# FIT_TCM_ATxmega.net
KiCad netlist of a schematic drawn in Altium Designer
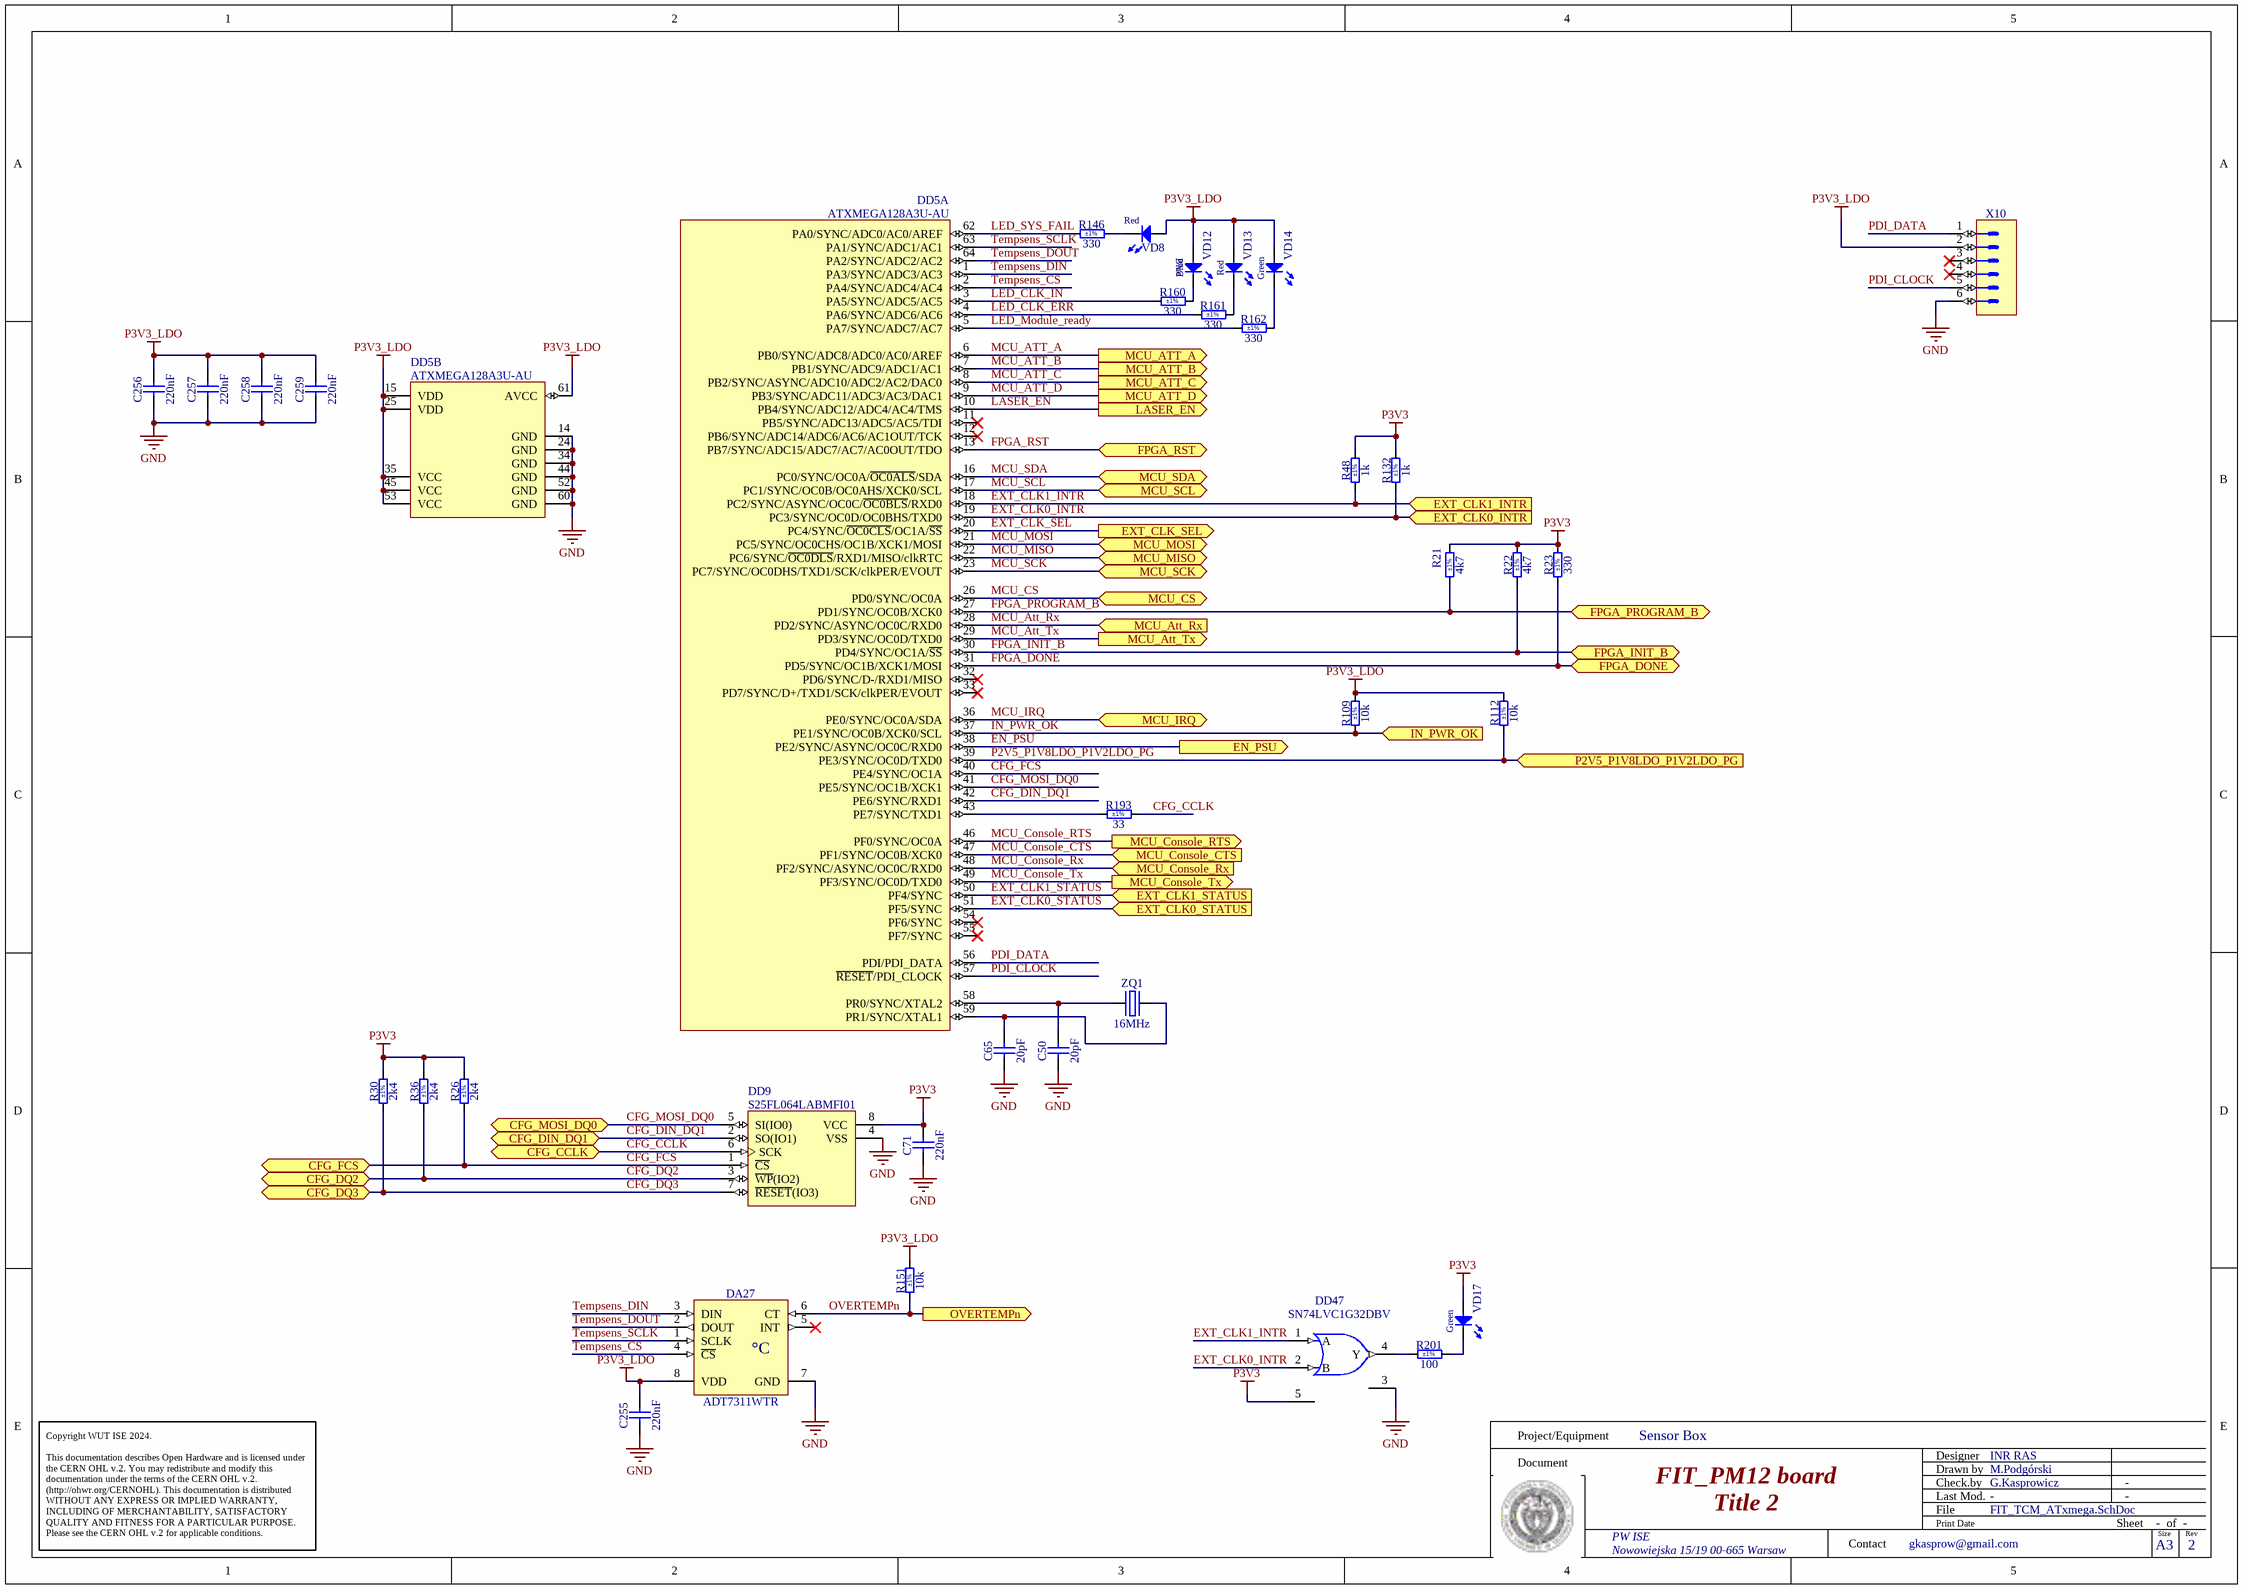
[diagram p0: FIT_TCM_ATxmega.SchDoc]

(export (version "E")
  (design (tool "Eeschema 10.0.6"))
  (components
    (comp (ref "C50")
      (value "20pF")
      (footprint "CAPC2012X135N")
      (description "Non-polarised capacitor")
      (fields
        (field (name "PART NUMBER") "CC0805_20PF_50V_2%_C0G")
        (field (name "VOLTAGE") "50V")
        (field (name "AUTHOR") "CERN DEM HF")
      )
      (libsource (lib "Capacitors") (part "Capacitor - non polarized"))
    )
    (comp (ref "C65")
      (value "20pF")
      (footprint "CAPC2012X135N")
      (description "Non-polarised capacitor")
      (fields
        (field (name "PART NUMBER") "CC0805_20PF_50V_2%_C0G")
        (field (name "VOLTAGE") "50V")
        (field (name "AUTHOR") "CERN DEM HF")
      )
      (libsource (lib "Capacitors") (part "Capacitor - non polarized"))
    )
    (comp (ref "C71")
      (value "220nF")
      (footprint "CAPC2012X135N")
      (description "Non-polarised capacitor")
      (fields
        (field (name "PART NUMBER") "CC0805_220NF_50V_10%_X7R")
        (field (name "VOLTAGE") "50V")
        (field (name "AUTHOR") "CERN DEM JLC")
      )
      (libsource (lib "Capacitors") (part "Capacitor - non polarized"))
    )
    (comp (ref "C255")
      (value "220nF")
      (footprint "CAPC2012X135N")
      (description "Non-polarised capacitor")
      (fields
        (field (name "PART NUMBER") "CC0805_220NF_50V_10%_X7R")
        (field (name "VOLTAGE") "50V")
        (field (name "AUTHOR") "CERN DEM JLC")
      )
      (libsource (lib "Capacitors") (part "Capacitor - non polarized"))
    )
    (comp (ref "C256")
      (value "220nF")
      (footprint "CAPC2012X135N")
      (description "Non-polarised capacitor")
      (fields
        (field (name "PART NUMBER") "CC0805_220NF_50V_10%_X7R")
        (field (name "VOLTAGE") "50V")
        (field (name "AUTHOR") "CERN DEM JLC")
      )
      (libsource (lib "Capacitors") (part "Capacitor - non polarized"))
    )
    (comp (ref "C257")
      (value "220nF")
      (footprint "CAPC2012X135N")
      (description "Non-polarised capacitor")
      (fields
        (field (name "PART NUMBER") "CC0805_220NF_50V_10%_X7R")
        (field (name "VOLTAGE") "50V")
        (field (name "AUTHOR") "CERN DEM JLC")
      )
      (libsource (lib "Capacitors") (part "Capacitor - non polarized"))
    )
    (comp (ref "C258")
      (value "220nF")
      (footprint "CAPC2012X135N")
      (description "Non-polarised capacitor")
      (fields
        (field (name "PART NUMBER") "CC0805_220NF_50V_10%_X7R")
        (field (name "VOLTAGE") "50V")
        (field (name "AUTHOR") "CERN DEM JLC")
      )
      (libsource (lib "Capacitors") (part "Capacitor - non polarized"))
    )
    (comp (ref "C259")
      (value "220nF")
      (footprint "CAPC2012X135N")
      (description "Non-polarised capacitor")
      (fields
        (field (name "PART NUMBER") "CC0805_220NF_50V_10%_X7R")
        (field (name "VOLTAGE") "50V")
        (field (name "AUTHOR") "CERN DEM JLC")
      )
      (libsource (lib "Capacitors") (part "Capacitor - non polarized"))
    )
    (comp (ref "DA27")
      (value "ADT7311WTR")
      (footprint "SOIC127P600X175-8N")
      (description "±0.5°C Accurate, 16-Bit Digital SPI Temperature Sensor")
      (fields (field (name "MANUFACTURER") "ANALOG DEVICES") (field (name "AUTHOR") "CERN DEM HF"))
      (libsource (lib "ICs And Semiconductors") (part "ADT7311WTR"))
    )
    (comp (ref "DD5")
      (value "ATXMEGA128A3U-AU")
      (footprint "QFP80P1600X1600X120-64N")
      (description "8/16-bit XMEGA A3BU 32MHz Microcontroller With 256KBytes of in-System Self-Programmable Flash")
      (fields (field (name "MANUFACTURER") "MICROCHIP TECHNOLOGY") (field (name "AUTHOR") "CERN DEM HF"))
      (libsource (lib "") (part "ATXMEGA128A3U-AU_1"))
    )
    (comp (ref "DD9")
      (value "S25FL064LABMFI01")
      (footprint "SOIC127P800X216-8N")
      (description "64 Mb (8 MB), 3V, FL-L SPI Flash Memory")
      (fields (field (name "MANUFACTURER") "INFINEON") (field (name "AUTHOR") "CERN DEM HF"))
      (libsource (lib "ICs And Semiconductors") (part "S25FL064LABMFI01"))
    )
    (comp (ref "DD47")
      (value "SN74LVC1G32DBV")
      (footprint "SOT95P280X145-5N")
      (description "Single 2-Input Positive-OR Gate")
      (fields
        (field (name "PART NUMBER") "SN74LVC1G32DBVR")
        (field (name "MANUFACTURER") "TEXAS INSTRUMENTS")
        (field (name "AUTHOR") "CERN DEM JLC")
      )
      (libsource (lib "ICs And Semiconductors") (part "741G32"))
    )
    (comp (ref "R21")
      (value "4k7")
      (footprint "RESC2012X60N")
      (description "Resistor - 1%")
      (fields
        (field (name "TOLERANCE") "±1%")
        (field (name "PART NUMBER") "R0805_4K7_1%_0.125W_100PPM")
        (field (name "POWER") "0.125W")
        (field (name "AUTHOR") "CERN DEM JLC")
      )
      (libsource (lib "Resistors") (part "Resistor - 1%"))
    )
    (comp (ref "R22")
      (value "4k7")
      (footprint "RESC2012X60N")
      (description "Resistor - 1%")
      (fields
        (field (name "TOLERANCE") "±1%")
        (field (name "PART NUMBER") "R0805_4K7_1%_0.125W_100PPM")
        (field (name "POWER") "0.125W")
        (field (name "AUTHOR") "CERN DEM JLC")
      )
      (libsource (lib "Resistors") (part "Resistor - 1%"))
    )
    (comp (ref "R23")
      (value "330")
      (footprint "RESC2012X60N")
      (description "Resistor - 1%")
      (fields
        (field (name "TOLERANCE") "±1%")
        (field (name "PART NUMBER") "R0805_330R_1%_0.125W_100PPM")
        (field (name "POWER") "0.125W")
        (field (name "AUTHOR") "CERN DEM JLC")
      )
      (libsource (lib "Resistors") (part "Resistor - 1%"))
    )
    (comp (ref "R26")
      (value "2k4")
      (footprint "RESC2012X60N")
      (description "Resistor - 1%")
      (fields
        (field (name "TOLERANCE") "±1%")
        (field (name "PART NUMBER") "R0805_2K4_1%_0.125W_100PPM")
        (field (name "POWER") "0.125W")
        (field (name "AUTHOR") "CERN DEM JLC")
      )
      (libsource (lib "Resistors") (part "Resistor - 1%"))
    )
    (comp (ref "R30")
      (value "2k4")
      (footprint "RESC2012X60N")
      (description "Resistor - 1%")
      (fields
        (field (name "TOLERANCE") "±1%")
        (field (name "PART NUMBER") "R0805_2K4_1%_0.125W_100PPM")
        (field (name "POWER") "0.125W")
        (field (name "AUTHOR") "CERN DEM JLC")
      )
      (libsource (lib "Resistors") (part "Resistor - 1%"))
    )
    (comp (ref "R36")
      (value "2k4")
      (footprint "RESC2012X60N")
      (description "Resistor - 1%")
      (fields
        (field (name "TOLERANCE") "±1%")
        (field (name "PART NUMBER") "R0805_2K4_1%_0.125W_100PPM")
        (field (name "POWER") "0.125W")
        (field (name "AUTHOR") "CERN DEM JLC")
      )
      (libsource (lib "Resistors") (part "Resistor - 1%"))
    )
    (comp (ref "R48")
      (value "1k")
      (footprint "RESC2012X60N")
      (description "Resistor - 1%")
      (fields
        (field (name "TOLERANCE") "±1%")
        (field (name "PART NUMBER") "R0805_1K_1%_0.125W_100PPM")
        (field (name "POWER") "0.125W")
        (field (name "AUTHOR") "CERN DEM JLC")
      )
      (libsource (lib "Resistors") (part "Resistor - 1%"))
    )
    (comp (ref "R109")
      (value "10k")
      (footprint "RESC2012X60N")
      (description "Resistor - 1%")
      (fields
        (field (name "TOLERANCE") "±1%")
        (field (name "PART NUMBER") "R0805_10K_1%_0.125W_100PPM")
        (field (name "POWER") "0.125W")
        (field (name "AUTHOR") "CERN DEM JLC")
      )
      (libsource (lib "Resistors") (part "Resistor - 1%"))
    )
    (comp (ref "R112")
      (value "10k")
      (footprint "RESC2012X60N")
      (description "Resistor - 1%")
      (fields
        (field (name "TOLERANCE") "±1%")
        (field (name "PART NUMBER") "R0805_10K_1%_0.125W_100PPM")
        (field (name "POWER") "0.125W")
        (field (name "AUTHOR") "CERN DEM JLC")
      )
      (libsource (lib "Resistors") (part "Resistor - 1%"))
    )
    (comp (ref "R132")
      (value "1k")
      (footprint "RESC2012X60N")
      (description "Resistor - 1%")
      (fields
        (field (name "TOLERANCE") "±1%")
        (field (name "PART NUMBER") "R0805_1K_1%_0.125W_100PPM")
        (field (name "POWER") "0.125W")
        (field (name "AUTHOR") "CERN DEM JLC")
      )
      (libsource (lib "Resistors") (part "Resistor - 1%"))
    )
    (comp (ref "R146")
      (value "330")
      (footprint "RESC2012X60N")
      (description "Resistor - 1%")
      (fields
        (field (name "TOLERANCE") "±1%")
        (field (name "PART NUMBER") "R0805_330R_1%_0.125W_100PPM")
        (field (name "POWER") "0.125W")
        (field (name "AUTHOR") "CERN DEM JLC")
      )
      (libsource (lib "Resistors") (part "Resistor - 1%"))
    )
    (comp (ref "R151")
      (value "10k")
      (footprint "RESC2012X60N")
      (description "Resistor - 1%")
      (fields
        (field (name "TOLERANCE") "±1%")
        (field (name "PART NUMBER") "R0805_10K_1%_0.125W_100PPM")
        (field (name "POWER") "0.125W")
        (field (name "AUTHOR") "CERN DEM JLC")
      )
      (libsource (lib "Resistors") (part "Resistor - 1%"))
    )
    (comp (ref "R160")
      (value "330")
      (footprint "RESC2012X60N")
      (description "Resistor - 1%")
      (fields
        (field (name "TOLERANCE") "±1%")
        (field (name "PART NUMBER") "R0805_330R_1%_0.125W_100PPM")
        (field (name "POWER") "0.125W")
        (field (name "AUTHOR") "CERN DEM JLC")
      )
      (libsource (lib "Resistors") (part "Resistor - 1%"))
    )
    (comp (ref "R161")
      (value "330")
      (footprint "RESC2012X60N")
      (description "Resistor - 1%")
      (fields
        (field (name "TOLERANCE") "±1%")
        (field (name "PART NUMBER") "R0805_330R_1%_0.125W_100PPM")
        (field (name "POWER") "0.125W")
        (field (name "AUTHOR") "CERN DEM JLC")
      )
      (libsource (lib "Resistors") (part "Resistor - 1%"))
    )
    (comp (ref "R162")
      (value "330")
      (footprint "RESC2012X60N")
      (description "Resistor - 1%")
      (fields
        (field (name "TOLERANCE") "±1%")
        (field (name "PART NUMBER") "R0805_330R_1%_0.125W_100PPM")
        (field (name "POWER") "0.125W")
        (field (name "AUTHOR") "CERN DEM JLC")
      )
      (libsource (lib "Resistors") (part "Resistor - 1%"))
    )
    (comp (ref "R193")
      (value "33")
      (footprint "RESC2012X60N")
      (description "Resistor - 1%")
      (fields
        (field (name "TOLERANCE") "±1%")
        (field (name "PART NUMBER") "R0805_33R_1%_0.125W_100PPM")
        (field (name "POWER") "0.125W")
        (field (name "AUTHOR") "CERN DEM JLC")
      )
      (libsource (lib "Resistors") (part "Resistor - 1%"))
    )
    (comp (ref "R201")
      (value "100")
      (footprint "RESC2012X60N")
      (description "Resistor - 1%")
      (fields
        (field (name "TOLERANCE") "±1%")
        (field (name "PART NUMBER") "R0805_100R_1%_0.125W_100PPM")
        (field (name "POWER") "0.125W")
        (field (name "AUTHOR") "CERN DEM JLC")
      )
      (libsource (lib "Resistors") (part "Resistor - 1%"))
    )
    (comp (ref "VD8")
      (value "Red")
      (footprint "LED_KINGBRIGHT_KPT-2012SURCK")
      (description "LED Red 1C 2A")
      (fields
        (field (name "PART NUMBER") "LED_KINGBRIGHT_KPT-2012SURCK")
        (field (name "MANUFACTURER") "KINGBRIGHT")
        (field (name "AUTHOR") "CERN DEM BC")
      )
      (libsource (lib "ICs And Semiconductors") (part "LED Red 1C 2A"))
    )
    (comp (ref "VD12")
      (value "Blue")
      (footprint "LED_KINGBRIGHT_KPT-2012VBC-D")
      (description "LED Blue 1C 2A")
      (fields
        (field (name "PART NUMBER") "LED_KINGBRIGHT_KPT-2012VBC-D")
        (field (name "MANUFACTURER") "KINGBRIGHT")
        (field (name "AUTHOR") "CERN DEM BC")
      )
      (libsource (lib "ICs And Semiconductors") (part "LED Blue 1C 2A"))
    )
    (comp (ref "VD13")
      (value "Red")
      (footprint "LED_KINGBRIGHT_KPT-2012SURCK")
      (description "LED Red 1C 2A")
      (fields
        (field (name "PART NUMBER") "LED_KINGBRIGHT_KPT-2012SURCK")
        (field (name "MANUFACTURER") "KINGBRIGHT")
        (field (name "AUTHOR") "CERN DEM BC")
      )
      (libsource (lib "ICs And Semiconductors") (part "LED Red 1C 2A"))
    )
    (comp (ref "VD14")
      (value "Green")
      (footprint "LED_KINGBRIGHT_KP-2012LSGC")
      (description "LED Green 1C 2A")
      (fields
        (field (name "PART NUMBER") "LED_KINGBRIGHT_KP-2012LSGC")
        (field (name "MANUFACTURER") "KINGBRIGHT")
        (field (name "AUTHOR") "CERN DEM BC")
      )
      (libsource (lib "ICs And Semiconductors") (part "LED Green 1C 2A"))
    )
    (comp (ref "VD17")
      (value "Green")
      (footprint "LED_KINGBRIGHT_KP-2012LSGC")
      (description "LED Green 1C 2A")
      (fields
        (field (name "PART NUMBER") "LED_KINGBRIGHT_KP-2012LSGC")
        (field (name "MANUFACTURER") "KINGBRIGHT")
        (field (name "AUTHOR") "CERN DEM BC")
      )
      (libsource (lib "ICs And Semiconductors") (part "LED Green 1C 2A"))
    )
    (comp (ref "X10")
      (value "~")
      (footprint "CONNFLY_DS1013-06SSIB1-B-0")
      (description "Connector 6 Male")
      (fields
        (field (name "PART NUMBER") "CONNFLY_DS1013-06SSIB1-B-0")
        (field (name "MANUFACTURER") "CONNFLY")
        (field (name "AUTHOR") "CERN DEM HF")
      )
      (libsource (lib "Connectors") (part "Connector 6 Male"))
    )
    (comp (ref "ZQ1")
      (value "16MHz")
      (footprint "XTAL_ABRACON_ABL")
      (description "Quartz Crystal")
      (fields
        (field (name "PART NUMBER") "XTAL_16MHZ_ABRACON_ABL-16.000MHZ-B1U")
        (field (name "MANUFACTURER") "ABRACON")
        (field (name "AUTHOR") "CERN DEM HF")
      )
      (libsource (lib "ICs And Semiconductors") (part "Quartz Crystal"))
    )
  )
  (nets
    (net (code "1") (name "/CFG_CCLK") (class "Default")
      (node (ref "DD9") (pin "6") (pinfunction "SCK_6") (pintype "input"))
      (node (ref "R193") (pin "2") (pinfunction "2_2") (pintype "passive"))
    )
    (net (code "2") (name "/CFG_DIN_DQ1") (class "Default")
      (node (ref "DD5") (pin "42") (pinfunction "PE6/SYNC/RXD1_42") (pintype "bidirectional"))
      (node (ref "DD9") (pin "2") (pinfunction "SO(IO1)_2") (pintype "bidirectional"))
    )
    (net (code "3") (name "/CFG_DQ2") (class "Default")
      (node (ref "DD9") (pin "3") (pinfunction "~{WP}(IO2)_3") (pintype "bidirectional"))
      (node (ref "R36") (pin "1") (pinfunction "1_1") (pintype "passive"))
    )
    (net (code "4") (name "/CFG_DQ3") (class "Default")
      (node (ref "DD9") (pin "7") (pinfunction "~{RESET}(IO3)_7") (pintype "bidirectional"))
      (node (ref "R30") (pin "1") (pinfunction "1_1") (pintype "passive"))
    )
    (net (code "5") (name "/CFG_FCS") (class "Default")
      (node (ref "DD5") (pin "40") (pinfunction "PE4/SYNC/OC1A_40") (pintype "bidirectional"))
      (node (ref "DD9") (pin "1") (pinfunction "~{CS}_1") (pintype "input"))
      (node (ref "R26") (pin "1") (pinfunction "1_1") (pintype "passive"))
    )
    (net (code "6") (name "/CFG_MOSI_DQ0") (class "Default")
      (node (ref "DD5") (pin "41") (pinfunction "PE5/SYNC/OC1B/XCK1_41") (pintype "bidirectional"))
      (node (ref "DD9") (pin "5") (pinfunction "SI(IO0)_5") (pintype "bidirectional"))
    )
    (net (code "7") (name "/EN_PSU") (class "Default")
      (node (ref "DD5") (pin "38") (pinfunction "PE2/SYNC/ASYNC/OC0C/RXD0_38") (pintype "bidirectional"))
    )
    (net (code "8") (name "/EXT_CLK0_INTR") (class "Default")
      (node (ref "DD47") (pin "2") (pinfunction "B_2") (pintype "input"))
      (node (ref "DD5") (pin "19") (pinfunction "PC3/SYNC/OC0D/OC0BHS/TXD0_19") (pintype "bidirectional"))
      (node (ref "R132") (pin "1") (pinfunction "1_1") (pintype "passive"))
    )
    (net (code "9") (name "/EXT_CLK0_STATUS") (class "Default")
      (node (ref "DD5") (pin "51") (pinfunction "PF5/SYNC_51") (pintype "bidirectional"))
    )
    (net (code "10") (name "/EXT_CLK1_INTR") (class "Default")
      (node (ref "DD47") (pin "1") (pinfunction "A_1") (pintype "input"))
      (node (ref "DD5") (pin "18") (pinfunction "PC2/SYNC/ASYNC/OC0C/~{OC0BLS}/RXD0_18") (pintype "bidirectional"))
      (node (ref "R48") (pin "1") (pinfunction "1_1") (pintype "passive"))
    )
    (net (code "11") (name "/EXT_CLK1_STATUS") (class "Default")
      (node (ref "DD5") (pin "50") (pinfunction "PF4/SYNC_50") (pintype "bidirectional"))
    )
    (net (code "12") (name "/EXT_CLK_SEL") (class "Default")
      (node (ref "DD5") (pin "20") (pinfunction "PC4/SYNC/~{OC0CLS}/OC1A/~{SS}_20") (pintype "bidirectional"))
    )
    (net (code "13") (name "/FPGA_DONE") (class "Default")
      (node (ref "DD5") (pin "31") (pinfunction "PD5/SYNC/OC1B/XCK1/MOSI_31") (pintype "bidirectional"))
      (node (ref "R23") (pin "1") (pinfunction "1_1") (pintype "passive"))
    )
    (net (code "14") (name "/FPGA_INIT_B") (class "Default")
      (node (ref "DD5") (pin "30") (pinfunction "PD4/SYNC/OC1A/~{SS}_30") (pintype "bidirectional"))
      (node (ref "R22") (pin "1") (pinfunction "1_1") (pintype "passive"))
    )
    (net (code "15") (name "/FPGA_PROGRAM_B") (class "Default")
      (node (ref "DD5") (pin "27") (pinfunction "PD1/SYNC/OC0B/XCK0_27") (pintype "bidirectional"))
      (node (ref "R21") (pin "1") (pinfunction "1_1") (pintype "passive"))
    )
    (net (code "16") (name "/FPGA_RST") (class "Default")
      (node (ref "DD5") (pin "13") (pinfunction "PB7/SYNC/ADC15/ADC7/AC7/AC0OUT/TDO_13") (pintype "bidirectional"))
    )
    (net (code "17") (name "/IN_PWR_OK") (class "Default")
      (node (ref "DD5") (pin "37") (pinfunction "PE1/SYNC/OC0B/XCK0/SCL_37") (pintype "bidirectional"))
      (node (ref "R109") (pin "1") (pinfunction "1_1") (pintype "passive"))
    )
    (net (code "18") (name "/LASER_EN") (class "Default")
      (node (ref "DD5") (pin "10") (pinfunction "PB4/SYNC/ADC12/ADC4/AC4/TMS_10") (pintype "bidirectional"))
    )
    (net (code "19") (name "/LED_CLK_ERR") (class "Default")
      (node (ref "DD5") (pin "4") (pinfunction "PA6/SYNC/ADC6/AC6_4") (pintype "bidirectional"))
      (node (ref "R161") (pin "1") (pinfunction "1_1") (pintype "passive"))
    )
    (net (code "20") (name "/LED_CLK_IN") (class "Default")
      (node (ref "DD5") (pin "3") (pinfunction "PA5/SYNC/ADC5/AC5_3") (pintype "bidirectional"))
      (node (ref "R160") (pin "1") (pinfunction "1_1") (pintype "passive"))
    )
    (net (code "21") (name "/LED_Module_ready") (class "Default")
      (node (ref "DD5") (pin "5") (pinfunction "PA7/SYNC/ADC7/AC7_5") (pintype "bidirectional"))
      (node (ref "R162") (pin "1") (pinfunction "1_1") (pintype "passive"))
    )
    (net (code "22") (name "/LED_SYS_FAIL") (class "Default")
      (node (ref "DD5") (pin "62") (pinfunction "PA0/SYNC/ADC0/AC0/AREF_62") (pintype "bidirectional"))
      (node (ref "R146") (pin "1") (pinfunction "1_1") (pintype "passive"))
    )
    (net (code "23") (name "/MCU_ATT_A") (class "Default")
      (node (ref "DD5") (pin "6") (pinfunction "PB0/SYNC/ADC8/ADC0/AC0/AREF_6") (pintype "bidirectional"))
    )
    (net (code "24") (name "/MCU_ATT_B") (class "Default")
      (node (ref "DD5") (pin "7") (pinfunction "PB1/SYNC/ADC9/ADC1/AC1_7") (pintype "bidirectional"))
    )
    (net (code "25") (name "/MCU_ATT_C") (class "Default")
      (node (ref "DD5") (pin "8") (pinfunction "PB2/SYNC/ASYNC/ADC10/ADC2/AC2/DAC0_8") (pintype "bidirectional"))
    )
    (net (code "26") (name "/MCU_ATT_D") (class "Default")
      (node (ref "DD5") (pin "9") (pinfunction "PB3/SYNC/ADC11/ADC3/AC3/DAC1_9") (pintype "bidirectional"))
    )
    (net (code "27") (name "/MCU_Att_Rx") (class "Default")
      (node (ref "DD5") (pin "28") (pinfunction "PD2/SYNC/ASYNC/OC0C/RXD0_28") (pintype "bidirectional"))
    )
    (net (code "28") (name "/MCU_Att_Tx") (class "Default")
      (node (ref "DD5") (pin "29") (pinfunction "PD3/SYNC/OC0D/TXD0_29") (pintype "bidirectional"))
    )
    (net (code "29") (name "/MCU_CS") (class "Default")
      (node (ref "DD5") (pin "26") (pinfunction "PD0/SYNC/OC0A_26") (pintype "bidirectional"))
    )
    (net (code "30") (name "/MCU_Console_CTS") (class "Default")
      (node (ref "DD5") (pin "47") (pinfunction "PF1/SYNC/OC0B/XCK0_47") (pintype "bidirectional"))
    )
    (net (code "31") (name "/MCU_Console_RTS") (class "Default")
      (node (ref "DD5") (pin "46") (pinfunction "PF0/SYNC/OC0A_46") (pintype "bidirectional"))
    )
    (net (code "32") (name "/MCU_Console_Rx") (class "Default")
      (node (ref "DD5") (pin "48") (pinfunction "PF2/SYNC/ASYNC/OC0C/RXD0_48") (pintype "bidirectional"))
    )
    (net (code "33") (name "/MCU_Console_Tx") (class "Default")
      (node (ref "DD5") (pin "49") (pinfunction "PF3/SYNC/OC0D/TXD0_49") (pintype "bidirectional"))
    )
    (net (code "34") (name "/MCU_IRQ") (class "Default")
      (node (ref "DD5") (pin "36") (pinfunction "PE0/SYNC/OC0A/SDA_36") (pintype "bidirectional"))
    )
    (net (code "35") (name "/MCU_MISO") (class "Default")
      (node (ref "DD5") (pin "22") (pinfunction "PC6/SYNC/~{OC0DLS}/RXD1/MISO/clkRTC_22") (pintype "bidirectional"))
    )
    (net (code "36") (name "/MCU_MOSI") (class "Default")
      (node (ref "DD5") (pin "21") (pinfunction "PC5/SYNC/OC0CHS/OC1B/XCK1/MOSI_21") (pintype "bidirectional"))
    )
    (net (code "37") (name "/MCU_SCK") (class "Default")
      (node (ref "DD5") (pin "23") (pinfunction "PC7/SYNC/OC0DHS/TXD1/SCK/clkPER/EVOUT_23") (pintype "bidirectional"))
    )
    (net (code "38") (name "/MCU_SCL") (class "Default")
      (node (ref "DD5") (pin "17") (pinfunction "PC1/SYNC/OC0B/OC0AHS/XCK0/SCL_17") (pintype "bidirectional"))
    )
    (net (code "39") (name "/MCU_SDA") (class "Default")
      (node (ref "DD5") (pin "16") (pinfunction "PC0/SYNC/OC0A/~{OC0ALS}/SDA_16") (pintype "bidirectional"))
    )
    (net (code "40") (name "/OVERTEMPn") (class "Default")
      (node (ref "DA27") (pin "6") (pinfunction "CT_6") (pintype "input"))
      (node (ref "R151") (pin "1") (pinfunction "1_1") (pintype "passive"))
    )
    (net (code "41") (name "/P2V5_P1V8LDO_P1V2LDO_PG") (class "Default")
      (node (ref "DD5") (pin "39") (pinfunction "PE3/SYNC/OC0D/TXD0_39") (pintype "bidirectional"))
      (node (ref "R112") (pin "1") (pinfunction "1_1") (pintype "passive"))
    )
    (net (code "42") (name "/PDI_CLOCK") (class "Default")
      (node (ref "DD5") (pin "57") (pinfunction "~{RESET}/PDI_CLOCK_57") (pintype "bidirectional"))
      (node (ref "X10") (pin "5") (pinfunction "5_5") (pintype "bidirectional"))
    )
    (net (code "43") (name "/PDI_DATA") (class "Default")
      (node (ref "DD5") (pin "56") (pinfunction "PDI/PDI_DATA_56") (pintype "bidirectional"))
      (node (ref "X10") (pin "1") (pinfunction "1_1") (pintype "bidirectional"))
    )
    (net (code "44") (name "/Tempsens_CS") (class "Default")
      (node (ref "DA27") (pin "4") (pinfunction "~{CS}_4") (pintype "input"))
      (node (ref "DD5") (pin "2") (pinfunction "PA4/SYNC/ADC4/AC4_2") (pintype "bidirectional"))
    )
    (net (code "45") (name "/Tempsens_DIN") (class "Default")
      (node (ref "DA27") (pin "3") (pinfunction "DIN_3") (pintype "input"))
      (node (ref "DD5") (pin "1") (pinfunction "PA3/SYNC/ADC3/AC3_1") (pintype "bidirectional"))
    )
    (net (code "46") (name "/Tempsens_DOUT") (class "Default")
      (node (ref "DA27") (pin "2") (pinfunction "DOUT_2") (pintype "output"))
      (node (ref "DD5") (pin "64") (pinfunction "PA2/SYNC/ADC2/AC2_64") (pintype "bidirectional"))
    )
    (net (code "47") (name "/Tempsens_SCLK") (class "Default")
      (node (ref "DA27") (pin "1") (pinfunction "SCLK_1") (pintype "input"))
      (node (ref "DD5") (pin "63") (pinfunction "PA1/SYNC/ADC1/AC1_63") (pintype "bidirectional"))
    )
    (net (code "48") (name "GND") (class "Default")
      (node (ref "C255") (pin "1") (pinfunction "1_1") (pintype "passive"))
      (node (ref "C256") (pin "1") (pinfunction "1_1") (pintype "passive"))
      (node (ref "C257") (pin "1") (pinfunction "1_1") (pintype "passive"))
      (node (ref "C258") (pin "1") (pinfunction "1_1") (pintype "passive"))
      (node (ref "C259") (pin "1") (pinfunction "1_1") (pintype "passive"))
      (node (ref "C50") (pin "1") (pinfunction "1_1") (pintype "passive"))
      (node (ref "C65") (pin "1") (pinfunction "1_1") (pintype "passive"))
      (node (ref "C71") (pin "1") (pinfunction "1_1") (pintype "passive"))
      (node (ref "DA27") (pin "7") (pinfunction "GND_7") (pintype "power_in"))
      (node (ref "DD47") (pin "3") (pinfunction "GND_3") (pintype "power_in"))
      (node (ref "DD5") (pin "14") (pinfunction "GND_14") (pintype "power_in"))
      (node (ref "DD5") (pin "24") (pinfunction "GND_24") (pintype "power_in"))
      (node (ref "DD5") (pin "34") (pinfunction "GND_34") (pintype "power_in"))
      (node (ref "DD5") (pin "44") (pinfunction "GND_44") (pintype "power_in"))
      (node (ref "DD5") (pin "52") (pinfunction "GND_52") (pintype "power_in"))
      (node (ref "DD5") (pin "60") (pinfunction "GND_60") (pintype "power_in"))
      (node (ref "DD9") (pin "4") (pinfunction "VSS_4") (pintype "power_in"))
      (node (ref "X10") (pin "6") (pinfunction "6_6") (pintype "bidirectional"))
    )
    (net (code "49") (name "Net-(DD5A-PE7{slash}SYNC{slash}TXD1)") (class "Default")
      (node (ref "DD5") (pin "43") (pinfunction "PE7/SYNC/TXD1_43") (pintype "bidirectional"))
      (node (ref "R193") (pin "1") (pinfunction "1_1") (pintype "passive"))
    )
    (net (code "50") (name "Net-(DD5A-PR0{slash}SYNC{slash}XTAL2)") (class "Default")
      (node (ref "C50") (pin "2") (pinfunction "2_2") (pintype "passive"))
      (node (ref "DD5") (pin "58") (pinfunction "PR0/SYNC/XTAL2_58") (pintype "bidirectional"))
      (node (ref "ZQ1") (pin "1") (pinfunction "OSC1_1") (pintype "passive"))
    )
    (net (code "51") (name "Net-(DD5A-PR1{slash}SYNC{slash}XTAL1)") (class "Default")
      (node (ref "C65") (pin "2") (pinfunction "2_2") (pintype "passive"))
      (node (ref "DD5") (pin "59") (pinfunction "PR1/SYNC/XTAL1_59") (pintype "bidirectional"))
      (node (ref "ZQ1") (pin "2") (pinfunction "OSC2_2") (pintype "passive"))
    )
    (net (code "52") (name "Net-(DD47-Y)") (class "Default")
      (node (ref "DD47") (pin "4") (pinfunction "Y_4") (pintype "output"))
      (node (ref "R201") (pin "1") (pinfunction "1_1") (pintype "passive"))
    )
    (net (code "53") (name "Net-(VD8-C)") (class "Default")
      (node (ref "R146") (pin "2") (pinfunction "2_2") (pintype "passive"))
      (node (ref "VD8") (pin "1") (pinfunction "C_1") (pintype "passive"))
    )
    (net (code "54") (name "Net-(VD12-C)") (class "Default")
      (node (ref "R160") (pin "2") (pinfunction "2_2") (pintype "passive"))
      (node (ref "VD12") (pin "1") (pinfunction "C_1") (pintype "passive"))
    )
    (net (code "55") (name "Net-(VD13-C)") (class "Default")
      (node (ref "R161") (pin "2") (pinfunction "2_2") (pintype "passive"))
      (node (ref "VD13") (pin "1") (pinfunction "C_1") (pintype "passive"))
    )
    (net (code "56") (name "Net-(VD14-C)") (class "Default")
      (node (ref "R162") (pin "2") (pinfunction "2_2") (pintype "passive"))
      (node (ref "VD14") (pin "1") (pinfunction "C_1") (pintype "passive"))
    )
    (net (code "57") (name "Net-(VD17-C)") (class "Default")
      (node (ref "R201") (pin "2") (pinfunction "2_2") (pintype "passive"))
      (node (ref "VD17") (pin "1") (pinfunction "C_1") (pintype "passive"))
    )
    (net (code "58") (name "P3V3") (class "Default")
      (node (ref "C71") (pin "2") (pinfunction "2_2") (pintype "passive"))
      (node (ref "DD47") (pin "5") (pinfunction "VCC_5") (pintype "power_in"))
      (node (ref "DD9") (pin "8") (pinfunction "VCC_8") (pintype "power_in"))
      (node (ref "R132") (pin "2") (pinfunction "2_2") (pintype "passive"))
      (node (ref "R21") (pin "2") (pinfunction "2_2") (pintype "passive"))
      (node (ref "R22") (pin "2") (pinfunction "2_2") (pintype "passive"))
      (node (ref "R23") (pin "2") (pinfunction "2_2") (pintype "passive"))
      (node (ref "R26") (pin "2") (pinfunction "2_2") (pintype "passive"))
      (node (ref "R30") (pin "2") (pinfunction "2_2") (pintype "passive"))
      (node (ref "R36") (pin "2") (pinfunction "2_2") (pintype "passive"))
      (node (ref "R48") (pin "2") (pinfunction "2_2") (pintype "passive"))
      (node (ref "VD17") (pin "2") (pinfunction "A_2") (pintype "passive"))
    )
    (net (code "59") (name "P3V3_LDO") (class "Default")
      (node (ref "C255") (pin "2") (pinfunction "2_2") (pintype "passive"))
      (node (ref "C256") (pin "2") (pinfunction "2_2") (pintype "passive"))
      (node (ref "C257") (pin "2") (pinfunction "2_2") (pintype "passive"))
      (node (ref "C258") (pin "2") (pinfunction "2_2") (pintype "passive"))
      (node (ref "C259") (pin "2") (pinfunction "2_2") (pintype "passive"))
      (node (ref "DA27") (pin "8") (pinfunction "VDD_8") (pintype "power_in"))
      (node (ref "DD5") (pin "15") (pinfunction "VDD_15") (pintype "power_in"))
      (node (ref "DD5") (pin "25") (pinfunction "VDD_25") (pintype "power_in"))
      (node (ref "DD5") (pin "35") (pinfunction "VCC_35") (pintype "power_in"))
      (node (ref "DD5") (pin "45") (pinfunction "VCC_45") (pintype "power_in"))
      (node (ref "DD5") (pin "53") (pinfunction "VCC_53") (pintype "power_in"))
      (node (ref "DD5") (pin "61") (pinfunction "AVCC_61") (pintype "bidirectional"))
      (node (ref "R109") (pin "2") (pinfunction "2_2") (pintype "passive"))
      (node (ref "R112") (pin "2") (pinfunction "2_2") (pintype "passive"))
      (node (ref "R151") (pin "2") (pinfunction "2_2") (pintype "passive"))
      (node (ref "VD12") (pin "2") (pinfunction "A_2") (pintype "passive"))
      (node (ref "VD13") (pin "2") (pinfunction "A_2") (pintype "passive"))
      (node (ref "VD14") (pin "2") (pinfunction "A_2") (pintype "passive"))
      (node (ref "VD8") (pin "2") (pinfunction "A_2") (pintype "passive"))
      (node (ref "X10") (pin "2") (pinfunction "2_2") (pintype "bidirectional"))
    )
    (net (code "60") (name "unconnected-(DA27-INT-Pad5)") (class "Default")
      (node (ref "DA27") (pin "5") (pinfunction "INT_5") (pintype "output+no_connect"))
    )
    (net (code "61") (name "unconnected-(DD5A-PB5{slash}SYNC{slash}ADC13{slash}ADC5{slash}AC5{slash}TDI-Pad11)") (class "Default")
      (node (ref "DD5") (pin "11") (pinfunction "PB5/SYNC/ADC13/ADC5/AC5/TDI_11") (pintype "bidirectional+no_connect"))
    )
    (net (code "62") (name "unconnected-(DD5A-PB6{slash}SYNC{slash}ADC14{slash}ADC6{slash}AC6{slash}AC1OUT{slash}TCK-Pad12)") (class "Default")
      (node (ref "DD5") (pin "12") (pinfunction "PB6/SYNC/ADC14/ADC6/AC6/AC1OUT/TCK_12") (pintype "bidirectional+no_connect"))
    )
    (net (code "63") (name "unconnected-(DD5A-PD6{slash}SYNC{slash}D-{slash}RXD1{slash}MISO-Pad32)") (class "Default")
      (node (ref "DD5") (pin "32") (pinfunction "PD6/SYNC/D-/RXD1/MISO_32") (pintype "bidirectional+no_connect"))
    )
    (net (code "64") (name "unconnected-(DD5A-PD7{slash}SYNC{slash}D+{slash}TXD1{slash}SCK{slash}clkPER{slash}EVOUT-Pad33)") (class "Default")
      (node (ref "DD5") (pin "33") (pinfunction "PD7/SYNC/D+/TXD1/SCK/clkPER/EVOUT_33") (pintype "bidirectional+no_connect"))
    )
    (net (code "65") (name "unconnected-(DD5A-PF6{slash}SYNC-Pad54)") (class "Default")
      (node (ref "DD5") (pin "54") (pinfunction "PF6/SYNC_54") (pintype "bidirectional+no_connect"))
    )
    (net (code "66") (name "unconnected-(DD5A-PF7{slash}SYNC-Pad55)") (class "Default")
      (node (ref "DD5") (pin "55") (pinfunction "PF7/SYNC_55") (pintype "bidirectional+no_connect"))
    )
    (net (code "67") (name "unconnected-(X10-Pad3)") (class "Default")
      (node (ref "X10") (pin "3") (pinfunction "3_3") (pintype "bidirectional+no_connect"))
    )
    (net (code "68") (name "unconnected-(X10-Pad4)") (class "Default")
      (node (ref "X10") (pin "4") (pinfunction "4_4") (pintype "bidirectional+no_connect"))
    )
  )
)
